# 8relays.net
KiCad netlist of a schematic drawn in EAGLE
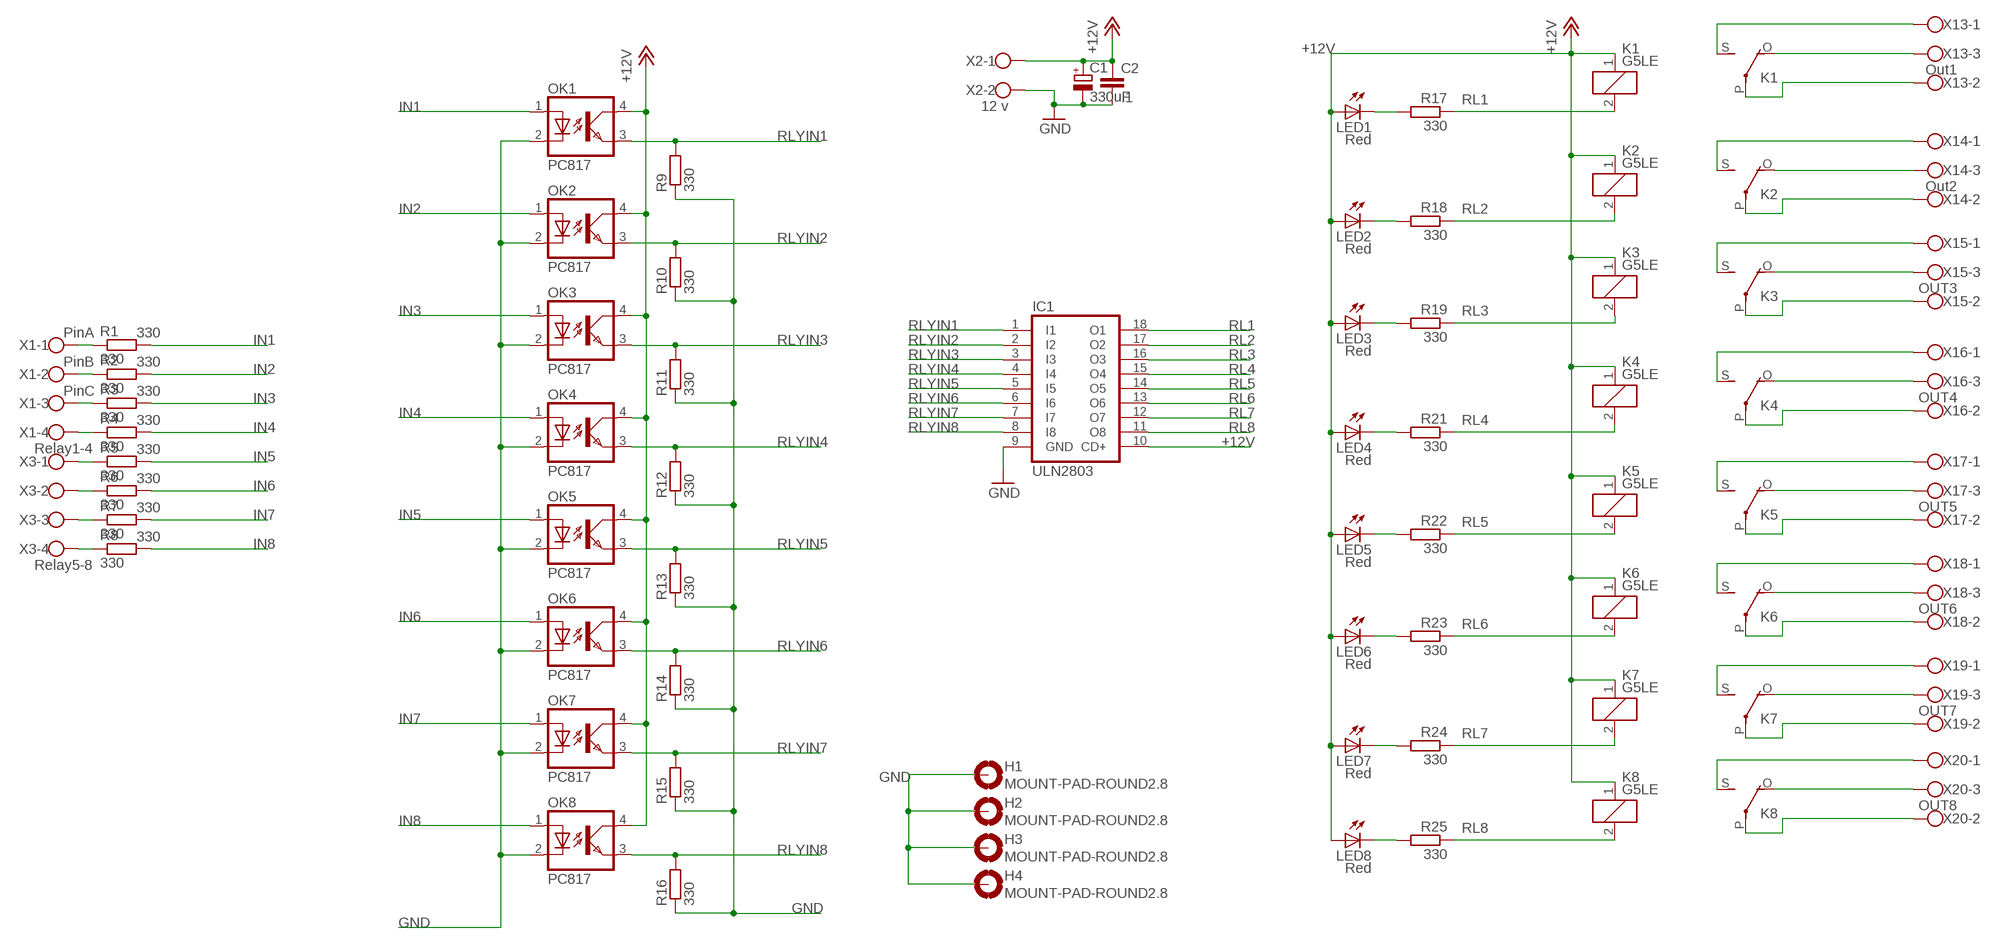
[diagram p0: schematic, sheet 1]

(export (version "E")
  (design (tool "Eeschema 10.0.6"))
  (components
    (comp (ref "C1")
      (value "330uF")
      (footprint "eagle-import:E5-10,5")
      (libsource (lib "eagle-import") (part "CPOL-EUE5-10.5"))
    )
    (comp (ref "C2")
      (value ".1")
      (footprint "eagle-import:C5B2.5")
      (libsource (lib "eagle-import") (part "C5/2.5"))
    )
    (comp (ref "H1")
      (value "MOUNT-PAD-ROUND2.8")
      (footprint "eagle-import:2,8-PAD")
      (libsource (lib "eagle-import") (part "MOUNT-PAD-ROUND2.8"))
    )
    (comp (ref "H2")
      (value "MOUNT-PAD-ROUND2.8")
      (footprint "eagle-import:2,8-PAD")
      (libsource (lib "eagle-import") (part "MOUNT-PAD-ROUND2.8"))
    )
    (comp (ref "H3")
      (value "MOUNT-PAD-ROUND2.8")
      (footprint "eagle-import:2,8-PAD")
      (libsource (lib "eagle-import") (part "MOUNT-PAD-ROUND2.8"))
    )
    (comp (ref "H4")
      (value "MOUNT-PAD-ROUND2.8")
      (footprint "eagle-import:2,8-PAD")
      (libsource (lib "eagle-import") (part "MOUNT-PAD-ROUND2.8"))
    )
    (comp (ref "IC1")
      (value "ULN2803")
      (footprint "eagle-import:DIL18")
      (libsource (lib "eagle-import") (part "ULN2803A"))
    )
    (comp (ref "K1")
      (value "G5LE")
      (footprint "eagle-import:G5LE")
      (libsource (lib "eagle-import") (part "G5LE"))
    )
    (comp (ref "K2")
      (value "G5LE")
      (footprint "eagle-import:G5LE")
      (libsource (lib "eagle-import") (part "G5LE"))
    )
    (comp (ref "K3")
      (value "G5LE")
      (footprint "eagle-import:G5LE")
      (libsource (lib "eagle-import") (part "G5LE"))
    )
    (comp (ref "K4")
      (value "G5LE")
      (footprint "eagle-import:G5LE")
      (libsource (lib "eagle-import") (part "G5LE"))
    )
    (comp (ref "K5")
      (value "G5LE")
      (footprint "eagle-import:G5LE")
      (libsource (lib "eagle-import") (part "G5LE"))
    )
    (comp (ref "K6")
      (value "G5LE")
      (footprint "eagle-import:G5LE")
      (libsource (lib "eagle-import") (part "G5LE"))
    )
    (comp (ref "K7")
      (value "G5LE")
      (footprint "eagle-import:G5LE")
      (libsource (lib "eagle-import") (part "G5LE"))
    )
    (comp (ref "K8")
      (value "G5LE")
      (footprint "eagle-import:G5LE")
      (libsource (lib "eagle-import") (part "G5LE"))
    )
    (comp (ref "LED1")
      (value "Red")
      (footprint "eagle-import:LED3MM")
      (libsource (lib "eagle-import") (part "LED3MM"))
    )
    (comp (ref "LED2")
      (value "Red")
      (footprint "eagle-import:LED3MM")
      (libsource (lib "eagle-import") (part "LED3MM"))
    )
    (comp (ref "LED3")
      (value "Red")
      (footprint "eagle-import:LED3MM")
      (libsource (lib "eagle-import") (part "LED3MM"))
    )
    (comp (ref "LED4")
      (value "Red")
      (footprint "eagle-import:LED3MM")
      (libsource (lib "eagle-import") (part "LED3MM"))
    )
    (comp (ref "LED5")
      (value "Red")
      (footprint "eagle-import:LED3MM")
      (libsource (lib "eagle-import") (part "LED3MM"))
    )
    (comp (ref "LED6")
      (value "Red")
      (footprint "eagle-import:LED3MM")
      (libsource (lib "eagle-import") (part "LED3MM"))
    )
    (comp (ref "LED7")
      (value "Red")
      (footprint "eagle-import:LED3MM")
      (libsource (lib "eagle-import") (part "LED3MM"))
    )
    (comp (ref "LED8")
      (value "Red")
      (footprint "eagle-import:LED3MM")
      (libsource (lib "eagle-import") (part "LED3MM"))
    )
    (comp (ref "OK1")
      (value "PC817")
      (footprint "eagle-import:DIL04")
      (libsource (lib "eagle-import") (part "PC817"))
    )
    (comp (ref "OK2")
      (value "PC817")
      (footprint "eagle-import:DIL04")
      (libsource (lib "eagle-import") (part "PC817"))
    )
    (comp (ref "OK3")
      (value "PC817")
      (footprint "eagle-import:DIL04")
      (libsource (lib "eagle-import") (part "PC817"))
    )
    (comp (ref "OK4")
      (value "PC817")
      (footprint "eagle-import:DIL04")
      (libsource (lib "eagle-import") (part "PC817"))
    )
    (comp (ref "OK5")
      (value "PC817")
      (footprint "eagle-import:DIL04")
      (libsource (lib "eagle-import") (part "PC817"))
    )
    (comp (ref "OK6")
      (value "PC817")
      (footprint "eagle-import:DIL04")
      (libsource (lib "eagle-import") (part "PC817"))
    )
    (comp (ref "OK7")
      (value "PC817")
      (footprint "eagle-import:DIL04")
      (libsource (lib "eagle-import") (part "PC817"))
    )
    (comp (ref "OK8")
      (value "PC817")
      (footprint "eagle-import:DIL04")
      (libsource (lib "eagle-import") (part "PC817"))
    )
    (comp (ref "R1")
      (value "330")
      (footprint "eagle-import:0204_5")
      (libsource (lib "eagle-import") (part "R-EU_0204/5"))
    )
    (comp (ref "R2")
      (value "330")
      (footprint "eagle-import:0204_5")
      (libsource (lib "eagle-import") (part "R-EU_0204/5"))
    )
    (comp (ref "R3")
      (value "330")
      (footprint "eagle-import:0204_5")
      (libsource (lib "eagle-import") (part "R-EU_0204/5"))
    )
    (comp (ref "R4")
      (value "330")
      (footprint "eagle-import:0204_5")
      (libsource (lib "eagle-import") (part "R-EU_0204/5"))
    )
    (comp (ref "R5")
      (value "330")
      (footprint "eagle-import:0204_5")
      (libsource (lib "eagle-import") (part "R-EU_0204/5"))
    )
    (comp (ref "R6")
      (value "330")
      (footprint "eagle-import:0204_5")
      (libsource (lib "eagle-import") (part "R-EU_0204/5"))
    )
    (comp (ref "R7")
      (value "330")
      (footprint "eagle-import:0204_5")
      (libsource (lib "eagle-import") (part "R-EU_0204/5"))
    )
    (comp (ref "R8")
      (value "330")
      (footprint "eagle-import:0204_5")
      (libsource (lib "eagle-import") (part "R-EU_0204/5"))
    )
    (comp (ref "R9")
      (value "330")
      (footprint "eagle-import:0204_5")
      (libsource (lib "eagle-import") (part "R-EU_0204/5"))
    )
    (comp (ref "R10")
      (value "330")
      (footprint "eagle-import:0204_5")
      (libsource (lib "eagle-import") (part "R-EU_0204/5"))
    )
    (comp (ref "R11")
      (value "330")
      (footprint "eagle-import:0204_5")
      (libsource (lib "eagle-import") (part "R-EU_0204/5"))
    )
    (comp (ref "R12")
      (value "330")
      (footprint "eagle-import:0204_5")
      (libsource (lib "eagle-import") (part "R-EU_0204/5"))
    )
    (comp (ref "R13")
      (value "330")
      (footprint "eagle-import:0204_5")
      (libsource (lib "eagle-import") (part "R-EU_0204/5"))
    )
    (comp (ref "R14")
      (value "330")
      (footprint "eagle-import:0204_5")
      (libsource (lib "eagle-import") (part "R-EU_0204/5"))
    )
    (comp (ref "R15")
      (value "330")
      (footprint "eagle-import:0204_5")
      (libsource (lib "eagle-import") (part "R-EU_0204/5"))
    )
    (comp (ref "R16")
      (value "330")
      (footprint "eagle-import:0204_5")
      (libsource (lib "eagle-import") (part "R-EU_0204/5"))
    )
    (comp (ref "R17")
      (value "330")
      (footprint "eagle-import:0204_5")
      (libsource (lib "eagle-import") (part "R-EU_0204/5"))
    )
    (comp (ref "R18")
      (value "330")
      (footprint "eagle-import:0204_5")
      (libsource (lib "eagle-import") (part "R-EU_0204/5"))
    )
    (comp (ref "R19")
      (value "330")
      (footprint "eagle-import:0204_5")
      (libsource (lib "eagle-import") (part "R-EU_0204/5"))
    )
    (comp (ref "R21")
      (value "330")
      (footprint "eagle-import:0204_5")
      (libsource (lib "eagle-import") (part "R-EU_0204/5"))
    )
    (comp (ref "R22")
      (value "330")
      (footprint "eagle-import:0204_5")
      (libsource (lib "eagle-import") (part "R-EU_0204/5"))
    )
    (comp (ref "R23")
      (value "330")
      (footprint "eagle-import:0204_5")
      (libsource (lib "eagle-import") (part "R-EU_0204/5"))
    )
    (comp (ref "R24")
      (value "330")
      (footprint "eagle-import:0204_5")
      (libsource (lib "eagle-import") (part "R-EU_0204/5"))
    )
    (comp (ref "R25")
      (value "330")
      (footprint "eagle-import:0204_5")
      (libsource (lib "eagle-import") (part "R-EU_0204/5"))
    )
    (comp (ref "X1")
      (value "Relay1-4")
      (footprint "eagle-import:W237-4")
      (libsource (lib "eagle-import") (part "W237-4"))
    )
    (comp (ref "X2")
      (value "12 v")
      (footprint "eagle-import:W237-102")
      (fields (field (name "MPN") "237-102"))
      (libsource (lib "eagle-import") (part "W237-102"))
    )
    (comp (ref "X3")
      (value "Relay5-8")
      (footprint "eagle-import:W237-4")
      (libsource (lib "eagle-import") (part "W237-4"))
    )
    (comp (ref "X13")
      (value "Out1")
      (footprint "eagle-import:W237-103")
      (fields (field (name "MPN") "237-103"))
      (libsource (lib "eagle-import") (part "W237-103"))
    )
    (comp (ref "X14")
      (value "Out2")
      (footprint "eagle-import:W237-103")
      (fields (field (name "MPN") "237-103"))
      (libsource (lib "eagle-import") (part "W237-103"))
    )
    (comp (ref "X15")
      (value "OUT3")
      (footprint "eagle-import:W237-103")
      (fields (field (name "MPN") "237-103"))
      (libsource (lib "eagle-import") (part "W237-103"))
    )
    (comp (ref "X16")
      (value "OUT4")
      (footprint "eagle-import:W237-103")
      (fields (field (name "MPN") "237-103"))
      (libsource (lib "eagle-import") (part "W237-103"))
    )
    (comp (ref "X17")
      (value "OUT5")
      (footprint "eagle-import:W237-103")
      (fields (field (name "MPN") "237-103"))
      (libsource (lib "eagle-import") (part "W237-103"))
    )
    (comp (ref "X18")
      (value "OUT6")
      (footprint "eagle-import:W237-103")
      (fields (field (name "MPN") "237-103"))
      (libsource (lib "eagle-import") (part "W237-103"))
    )
    (comp (ref "X19")
      (value "OUT7")
      (footprint "eagle-import:W237-103")
      (fields (field (name "MPN") "237-103"))
      (libsource (lib "eagle-import") (part "W237-103"))
    )
    (comp (ref "X20")
      (value "OUT8")
      (footprint "eagle-import:W237-103")
      (fields (field (name "MPN") "237-103"))
      (libsource (lib "eagle-import") (part "W237-103"))
    )
  )
  (nets
    (net (code "1") (name "+12V") (class "Default")
      (node (ref "C1") (pin "+") (pinfunction "+_+") (pintype "passive"))
      (node (ref "C2") (pin "1") (pinfunction "1_1") (pintype "passive"))
      (node (ref "IC1") (pin "10") (pinfunction "CD+_10") (pintype "passive"))
      (node (ref "K1") (pin "1") (pinfunction "1_1") (pintype "passive"))
      (node (ref "K2") (pin "1") (pinfunction "1_1") (pintype "passive"))
      (node (ref "K3") (pin "1") (pinfunction "1_1") (pintype "passive"))
      (node (ref "K4") (pin "1") (pinfunction "1_1") (pintype "passive"))
      (node (ref "K5") (pin "1") (pinfunction "1_1") (pintype "passive"))
      (node (ref "K6") (pin "1") (pinfunction "1_1") (pintype "passive"))
      (node (ref "K7") (pin "1") (pinfunction "1_1") (pintype "passive"))
      (node (ref "K8") (pin "1") (pinfunction "1_1") (pintype "passive"))
      (node (ref "LED1") (pin "A") (pinfunction "A_A") (pintype "passive"))
      (node (ref "LED2") (pin "A") (pinfunction "A_A") (pintype "passive"))
      (node (ref "LED3") (pin "A") (pinfunction "A_A") (pintype "passive"))
      (node (ref "LED4") (pin "A") (pinfunction "A_A") (pintype "passive"))
      (node (ref "LED5") (pin "A") (pinfunction "A_A") (pintype "passive"))
      (node (ref "LED6") (pin "A") (pinfunction "A_A") (pintype "passive"))
      (node (ref "LED7") (pin "A") (pinfunction "A_A") (pintype "passive"))
      (node (ref "LED8") (pin "A") (pinfunction "A_A") (pintype "passive"))
      (node (ref "OK1") (pin "4") (pinfunction "COL_4") (pintype "passive"))
      (node (ref "OK2") (pin "4") (pinfunction "COL_4") (pintype "passive"))
      (node (ref "OK3") (pin "4") (pinfunction "COL_4") (pintype "passive"))
      (node (ref "OK4") (pin "4") (pinfunction "COL_4") (pintype "passive"))
      (node (ref "OK5") (pin "4") (pinfunction "COL_4") (pintype "passive"))
      (node (ref "OK6") (pin "4") (pinfunction "COL_4") (pintype "passive"))
      (node (ref "OK7") (pin "4") (pinfunction "COL_4") (pintype "passive"))
      (node (ref "OK8") (pin "4") (pinfunction "COL_4") (pintype "passive"))
      (node (ref "X2") (pin "1") (pinfunction "KL_1") (pintype "passive"))
    )
    (net (code "2") (name "/IN1") (class "Default")
      (node (ref "OK1") (pin "1") (pinfunction "A_1") (pintype "passive"))
      (node (ref "R1") (pin "2") (pinfunction "2_2") (pintype "passive"))
    )
    (net (code "3") (name "/IN2") (class "Default")
      (node (ref "OK2") (pin "1") (pinfunction "A_1") (pintype "passive"))
      (node (ref "R2") (pin "2") (pinfunction "2_2") (pintype "passive"))
    )
    (net (code "4") (name "/IN3") (class "Default")
      (node (ref "OK3") (pin "1") (pinfunction "A_1") (pintype "passive"))
      (node (ref "R3") (pin "2") (pinfunction "2_2") (pintype "passive"))
    )
    (net (code "5") (name "/IN4") (class "Default")
      (node (ref "OK4") (pin "1") (pinfunction "A_1") (pintype "passive"))
      (node (ref "R4") (pin "2") (pinfunction "2_2") (pintype "passive"))
    )
    (net (code "6") (name "/IN5") (class "Default")
      (node (ref "OK5") (pin "1") (pinfunction "A_1") (pintype "passive"))
      (node (ref "R5") (pin "2") (pinfunction "2_2") (pintype "passive"))
    )
    (net (code "7") (name "/IN6") (class "Default")
      (node (ref "OK6") (pin "1") (pinfunction "A_1") (pintype "passive"))
      (node (ref "R6") (pin "2") (pinfunction "2_2") (pintype "passive"))
    )
    (net (code "8") (name "/IN7") (class "Default")
      (node (ref "OK7") (pin "1") (pinfunction "A_1") (pintype "passive"))
      (node (ref "R7") (pin "2") (pinfunction "2_2") (pintype "passive"))
    )
    (net (code "9") (name "/IN8") (class "Default")
      (node (ref "OK8") (pin "1") (pinfunction "A_1") (pintype "passive"))
      (node (ref "R8") (pin "2") (pinfunction "2_2") (pintype "passive"))
    )
    (net (code "10") (name "/RL1") (class "Default")
      (node (ref "IC1") (pin "18") (pinfunction "O1_18") (pintype "open_collector"))
      (node (ref "K1") (pin "2") (pinfunction "2_2") (pintype "passive"))
      (node (ref "R17") (pin "1") (pinfunction "1_1") (pintype "passive"))
    )
    (net (code "11") (name "/RL2") (class "Default")
      (node (ref "IC1") (pin "17") (pinfunction "O2_17") (pintype "open_collector"))
      (node (ref "K2") (pin "2") (pinfunction "2_2") (pintype "passive"))
      (node (ref "R18") (pin "1") (pinfunction "1_1") (pintype "passive"))
    )
    (net (code "12") (name "/RL3") (class "Default")
      (node (ref "IC1") (pin "16") (pinfunction "O3_16") (pintype "open_collector"))
      (node (ref "K3") (pin "2") (pinfunction "2_2") (pintype "passive"))
      (node (ref "R19") (pin "1") (pinfunction "1_1") (pintype "passive"))
    )
    (net (code "13") (name "/RL4") (class "Default")
      (node (ref "IC1") (pin "15") (pinfunction "O4_15") (pintype "open_collector"))
      (node (ref "K4") (pin "2") (pinfunction "2_2") (pintype "passive"))
      (node (ref "R21") (pin "1") (pinfunction "1_1") (pintype "passive"))
    )
    (net (code "14") (name "/RL5") (class "Default")
      (node (ref "IC1") (pin "14") (pinfunction "O5_14") (pintype "open_collector"))
      (node (ref "K5") (pin "2") (pinfunction "2_2") (pintype "passive"))
      (node (ref "R22") (pin "1") (pinfunction "1_1") (pintype "passive"))
    )
    (net (code "15") (name "/RL6") (class "Default")
      (node (ref "IC1") (pin "13") (pinfunction "O6_13") (pintype "open_collector"))
      (node (ref "K6") (pin "2") (pinfunction "2_2") (pintype "passive"))
      (node (ref "R23") (pin "1") (pinfunction "1_1") (pintype "passive"))
    )
    (net (code "16") (name "/RL7") (class "Default")
      (node (ref "IC1") (pin "12") (pinfunction "O7_12") (pintype "open_collector"))
      (node (ref "K7") (pin "2") (pinfunction "2_2") (pintype "passive"))
      (node (ref "R24") (pin "1") (pinfunction "1_1") (pintype "passive"))
    )
    (net (code "17") (name "/RL8") (class "Default")
      (node (ref "IC1") (pin "11") (pinfunction "O8_11") (pintype "open_collector"))
      (node (ref "K8") (pin "2") (pinfunction "2_2") (pintype "passive"))
      (node (ref "R25") (pin "1") (pinfunction "1_1") (pintype "passive"))
    )
    (net (code "18") (name "/RLYIN1") (class "Default")
      (node (ref "IC1") (pin "1") (pinfunction "I1_1") (pintype "input"))
      (node (ref "OK1") (pin "3") (pinfunction "EMIT_3") (pintype "passive"))
      (node (ref "R9") (pin "2") (pinfunction "2_2") (pintype "passive"))
    )
    (net (code "19") (name "/RLYIN2") (class "Default")
      (node (ref "IC1") (pin "2") (pinfunction "I2_2") (pintype "input"))
      (node (ref "OK2") (pin "3") (pinfunction "EMIT_3") (pintype "passive"))
      (node (ref "R10") (pin "2") (pinfunction "2_2") (pintype "passive"))
    )
    (net (code "20") (name "/RLYIN3") (class "Default")
      (node (ref "IC1") (pin "3") (pinfunction "I3_3") (pintype "input"))
      (node (ref "OK3") (pin "3") (pinfunction "EMIT_3") (pintype "passive"))
      (node (ref "R11") (pin "2") (pinfunction "2_2") (pintype "passive"))
    )
    (net (code "21") (name "/RLYIN4") (class "Default")
      (node (ref "IC1") (pin "4") (pinfunction "I4_4") (pintype "input"))
      (node (ref "OK4") (pin "3") (pinfunction "EMIT_3") (pintype "passive"))
      (node (ref "R12") (pin "2") (pinfunction "2_2") (pintype "passive"))
    )
    (net (code "22") (name "/RLYIN5") (class "Default")
      (node (ref "IC1") (pin "5") (pinfunction "I5_5") (pintype "input"))
      (node (ref "OK5") (pin "3") (pinfunction "EMIT_3") (pintype "passive"))
      (node (ref "R13") (pin "2") (pinfunction "2_2") (pintype "passive"))
    )
    (net (code "23") (name "/RLYIN6") (class "Default")
      (node (ref "IC1") (pin "6") (pinfunction "I6_6") (pintype "input"))
      (node (ref "OK6") (pin "3") (pinfunction "EMIT_3") (pintype "passive"))
      (node (ref "R14") (pin "2") (pinfunction "2_2") (pintype "passive"))
    )
    (net (code "24") (name "/RLYIN7") (class "Default")
      (node (ref "IC1") (pin "7") (pinfunction "I7_7") (pintype "input"))
      (node (ref "OK7") (pin "3") (pinfunction "EMIT_3") (pintype "passive"))
      (node (ref "R15") (pin "2") (pinfunction "2_2") (pintype "passive"))
    )
    (net (code "25") (name "/RLYIN8") (class "Default")
      (node (ref "IC1") (pin "8") (pinfunction "I8_8") (pintype "input"))
      (node (ref "OK8") (pin "3") (pinfunction "EMIT_3") (pintype "passive"))
      (node (ref "R16") (pin "2") (pinfunction "2_2") (pintype "passive"))
    )
    (net (code "26") (name "GND") (class "Default")
      (node (ref "C1") (pin "-") (pinfunction "-_-") (pintype "passive"))
      (node (ref "C2") (pin "2") (pinfunction "2_2") (pintype "passive"))
      (node (ref "H1") (pin "B2,8") (pinfunction "MOUNT_B2,8") (pintype "passive"))
      (node (ref "H2") (pin "B2,8") (pinfunction "MOUNT_B2,8") (pintype "passive"))
      (node (ref "H3") (pin "B2,8") (pinfunction "MOUNT_B2,8") (pintype "passive"))
      (node (ref "H4") (pin "B2,8") (pinfunction "MOUNT_B2,8") (pintype "passive"))
      (node (ref "IC1") (pin "9") (pinfunction "GND_9") (pintype "power_in"))
      (node (ref "OK1") (pin "2") (pinfunction "C_2") (pintype "passive"))
      (node (ref "OK2") (pin "2") (pinfunction "C_2") (pintype "passive"))
      (node (ref "OK3") (pin "2") (pinfunction "C_2") (pintype "passive"))
      (node (ref "OK4") (pin "2") (pinfunction "C_2") (pintype "passive"))
      (node (ref "OK5") (pin "2") (pinfunction "C_2") (pintype "passive"))
      (node (ref "OK6") (pin "2") (pinfunction "C_2") (pintype "passive"))
      (node (ref "OK7") (pin "2") (pinfunction "C_2") (pintype "passive"))
      (node (ref "OK8") (pin "2") (pinfunction "C_2") (pintype "passive"))
      (node (ref "R10") (pin "1") (pinfunction "1_1") (pintype "passive"))
      (node (ref "R11") (pin "1") (pinfunction "1_1") (pintype "passive"))
      (node (ref "R12") (pin "1") (pinfunction "1_1") (pintype "passive"))
      (node (ref "R13") (pin "1") (pinfunction "1_1") (pintype "passive"))
      (node (ref "R14") (pin "1") (pinfunction "1_1") (pintype "passive"))
      (node (ref "R15") (pin "1") (pinfunction "1_1") (pintype "passive"))
      (node (ref "R16") (pin "1") (pinfunction "1_1") (pintype "passive"))
      (node (ref "R9") (pin "1") (pinfunction "1_1") (pintype "passive"))
      (node (ref "X2") (pin "2") (pinfunction "KL_2") (pintype "passive"))
    )
    (net (code "27") (name "Net-(LED1-C)") (class "Default")
      (node (ref "LED1") (pin "K") (pinfunction "C_K") (pintype "passive"))
      (node (ref "R17") (pin "2") (pinfunction "2_2") (pintype "passive"))
    )
    (net (code "28") (name "Net-(LED2-C)") (class "Default")
      (node (ref "LED2") (pin "K") (pinfunction "C_K") (pintype "passive"))
      (node (ref "R18") (pin "2") (pinfunction "2_2") (pintype "passive"))
    )
    (net (code "29") (name "Net-(LED3-C)") (class "Default")
      (node (ref "LED3") (pin "K") (pinfunction "C_K") (pintype "passive"))
      (node (ref "R19") (pin "2") (pinfunction "2_2") (pintype "passive"))
    )
    (net (code "30") (name "Net-(LED4-C)") (class "Default")
      (node (ref "LED4") (pin "K") (pinfunction "C_K") (pintype "passive"))
      (node (ref "R21") (pin "2") (pinfunction "2_2") (pintype "passive"))
    )
    (net (code "31") (name "Net-(LED5-C)") (class "Default")
      (node (ref "LED5") (pin "K") (pinfunction "C_K") (pintype "passive"))
      (node (ref "R22") (pin "2") (pinfunction "2_2") (pintype "passive"))
    )
    (net (code "32") (name "Net-(LED6-C)") (class "Default")
      (node (ref "LED6") (pin "K") (pinfunction "C_K") (pintype "passive"))
      (node (ref "R23") (pin "2") (pinfunction "2_2") (pintype "passive"))
    )
    (net (code "33") (name "Net-(LED7-C)") (class "Default")
      (node (ref "LED7") (pin "K") (pinfunction "C_K") (pintype "passive"))
      (node (ref "R24") (pin "2") (pinfunction "2_2") (pintype "passive"))
    )
    (net (code "34") (name "Net-(LED8-C)") (class "Default")
      (node (ref "LED8") (pin "K") (pinfunction "C_K") (pintype "passive"))
      (node (ref "R25") (pin "2") (pinfunction "2_2") (pintype "passive"))
    )
    (net (code "35") (name "Net-(X1A-KL)") (class "Default")
      (node (ref "R1") (pin "1") (pinfunction "1_1") (pintype "passive"))
      (node (ref "X1") (pin "1") (pinfunction "KL_1") (pintype "passive"))
    )
    (net (code "36") (name "Net-(X1B-KL)") (class "Default")
      (node (ref "R2") (pin "1") (pinfunction "1_1") (pintype "passive"))
      (node (ref "X1") (pin "2") (pinfunction "KL_2") (pintype "passive"))
    )
    (net (code "37") (name "Net-(X1C-KL)") (class "Default")
      (node (ref "R3") (pin "1") (pinfunction "1_1") (pintype "passive"))
      (node (ref "X1") (pin "3") (pinfunction "KL_3") (pintype "passive"))
    )
    (net (code "38") (name "Net-(X1D-KL)") (class "Default")
      (node (ref "R4") (pin "1") (pinfunction "1_1") (pintype "passive"))
      (node (ref "X1") (pin "4") (pinfunction "KL_4") (pintype "passive"))
    )
    (net (code "39") (name "Net-(X3A-KL)") (class "Default")
      (node (ref "R5") (pin "1") (pinfunction "1_1") (pintype "passive"))
      (node (ref "X3") (pin "1") (pinfunction "KL_1") (pintype "passive"))
    )
    (net (code "40") (name "Net-(X3B-KL)") (class "Default")
      (node (ref "R6") (pin "1") (pinfunction "1_1") (pintype "passive"))
      (node (ref "X3") (pin "2") (pinfunction "KL_2") (pintype "passive"))
    )
    (net (code "41") (name "Net-(X3C-KL)") (class "Default")
      (node (ref "R7") (pin "1") (pinfunction "1_1") (pintype "passive"))
      (node (ref "X3") (pin "3") (pinfunction "KL_3") (pintype "passive"))
    )
    (net (code "42") (name "Net-(X3D-KL)") (class "Default")
      (node (ref "R8") (pin "1") (pinfunction "1_1") (pintype "passive"))
      (node (ref "X3") (pin "4") (pinfunction "KL_4") (pintype "passive"))
    )
    (net (code "43") (name "Net-(X13A-KL)") (class "Default")
      (node (ref "K1") (pin "S") (pinfunction "S_S") (pintype "passive"))
      (node (ref "X13") (pin "1") (pinfunction "KL_1") (pintype "passive"))
    )
    (net (code "44") (name "Net-(X13B-KL)") (class "Default")
      (node (ref "K1") (pin "P") (pinfunction "P_P") (pintype "passive"))
      (node (ref "X13") (pin "2") (pinfunction "KL_2") (pintype "passive"))
    )
    (net (code "45") (name "Net-(X13C-KL)") (class "Default")
      (node (ref "K1") (pin "O") (pinfunction "O_O") (pintype "passive"))
      (node (ref "X13") (pin "3") (pinfunction "KL_3") (pintype "passive"))
    )
    (net (code "46") (name "Net-(X14A-KL)") (class "Default")
      (node (ref "K2") (pin "S") (pinfunction "S_S") (pintype "passive"))
      (node (ref "X14") (pin "1") (pinfunction "KL_1") (pintype "passive"))
    )
    (net (code "47") (name "Net-(X14B-KL)") (class "Default")
      (node (ref "K2") (pin "P") (pinfunction "P_P") (pintype "passive"))
      (node (ref "X14") (pin "2") (pinfunction "KL_2") (pintype "passive"))
    )
    (net (code "48") (name "Net-(X14C-KL)") (class "Default")
      (node (ref "K2") (pin "O") (pinfunction "O_O") (pintype "passive"))
      (node (ref "X14") (pin "3") (pinfunction "KL_3") (pintype "passive"))
    )
    (net (code "49") (name "Net-(X15A-KL)") (class "Default")
      (node (ref "K3") (pin "S") (pinfunction "S_S") (pintype "passive"))
      (node (ref "X15") (pin "1") (pinfunction "KL_1") (pintype "passive"))
    )
    (net (code "50") (name "Net-(X15B-KL)") (class "Default")
      (node (ref "K3") (pin "P") (pinfunction "P_P") (pintype "passive"))
      (node (ref "X15") (pin "2") (pinfunction "KL_2") (pintype "passive"))
    )
    (net (code "51") (name "Net-(X15C-KL)") (class "Default")
      (node (ref "K3") (pin "O") (pinfunction "O_O") (pintype "passive"))
      (node (ref "X15") (pin "3") (pinfunction "KL_3") (pintype "passive"))
    )
    (net (code "52") (name "Net-(X16A-KL)") (class "Default")
      (node (ref "K4") (pin "S") (pinfunction "S_S") (pintype "passive"))
      (node (ref "X16") (pin "1") (pinfunction "KL_1") (pintype "passive"))
    )
    (net (code "53") (name "Net-(X16B-KL)") (class "Default")
      (node (ref "K4") (pin "P") (pinfunction "P_P") (pintype "passive"))
      (node (ref "X16") (pin "2") (pinfunction "KL_2") (pintype "passive"))
    )
    (net (code "54") (name "Net-(X16C-KL)") (class "Default")
      (node (ref "K4") (pin "O") (pinfunction "O_O") (pintype "passive"))
      (node (ref "X16") (pin "3") (pinfunction "KL_3") (pintype "passive"))
    )
    (net (code "55") (name "Net-(X17A-KL)") (class "Default")
      (node (ref "K5") (pin "S") (pinfunction "S_S") (pintype "passive"))
      (node (ref "X17") (pin "1") (pinfunction "KL_1") (pintype "passive"))
    )
    (net (code "56") (name "Net-(X17B-KL)") (class "Default")
      (node (ref "K5") (pin "P") (pinfunction "P_P") (pintype "passive"))
      (node (ref "X17") (pin "2") (pinfunction "KL_2") (pintype "passive"))
    )
    (net (code "57") (name "Net-(X17C-KL)") (class "Default")
      (node (ref "K5") (pin "O") (pinfunction "O_O") (pintype "passive"))
      (node (ref "X17") (pin "3") (pinfunction "KL_3") (pintype "passive"))
    )
    (net (code "58") (name "Net-(X18A-KL)") (class "Default")
      (node (ref "K6") (pin "S") (pinfunction "S_S") (pintype "passive"))
      (node (ref "X18") (pin "1") (pinfunction "KL_1") (pintype "passive"))
    )
    (net (code "59") (name "Net-(X18B-KL)") (class "Default")
      (node (ref "K6") (pin "P") (pinfunction "P_P") (pintype "passive"))
      (node (ref "X18") (pin "2") (pinfunction "KL_2") (pintype "passive"))
    )
    (net (code "60") (name "Net-(X18C-KL)") (class "Default")
      (node (ref "K6") (pin "O") (pinfunction "O_O") (pintype "passive"))
      (node (ref "X18") (pin "3") (pinfunction "KL_3") (pintype "passive"))
    )
    (net (code "61") (name "Net-(X19A-KL)") (class "Default")
      (node (ref "K7") (pin "S") (pinfunction "S_S") (pintype "passive"))
      (node (ref "X19") (pin "1") (pinfunction "KL_1") (pintype "passive"))
    )
    (net (code "62") (name "Net-(X19B-KL)") (class "Default")
      (node (ref "K7") (pin "P") (pinfunction "P_P") (pintype "passive"))
      (node (ref "X19") (pin "2") (pinfunction "KL_2") (pintype "passive"))
    )
    (net (code "63") (name "Net-(X19C-KL)") (class "Default")
      (node (ref "K7") (pin "O") (pinfunction "O_O") (pintype "passive"))
      (node (ref "X19") (pin "3") (pinfunction "KL_3") (pintype "passive"))
    )
    (net (code "64") (name "Net-(X20A-KL)") (class "Default")
      (node (ref "K8") (pin "S") (pinfunction "S_S") (pintype "passive"))
      (node (ref "X20") (pin "1") (pinfunction "KL_1") (pintype "passive"))
    )
    (net (code "65") (name "Net-(X20B-KL)") (class "Default")
      (node (ref "K8") (pin "P") (pinfunction "P_P") (pintype "passive"))
      (node (ref "X20") (pin "2") (pinfunction "KL_2") (pintype "passive"))
    )
    (net (code "66") (name "Net-(X20C-KL)") (class "Default")
      (node (ref "K8") (pin "O") (pinfunction "O_O") (pintype "passive"))
      (node (ref "X20") (pin "3") (pinfunction "KL_3") (pintype "passive"))
    )
  )
)
